# RpiXBeeDaughter.net
KiCad netlist of a schematic drawn in EAGLE
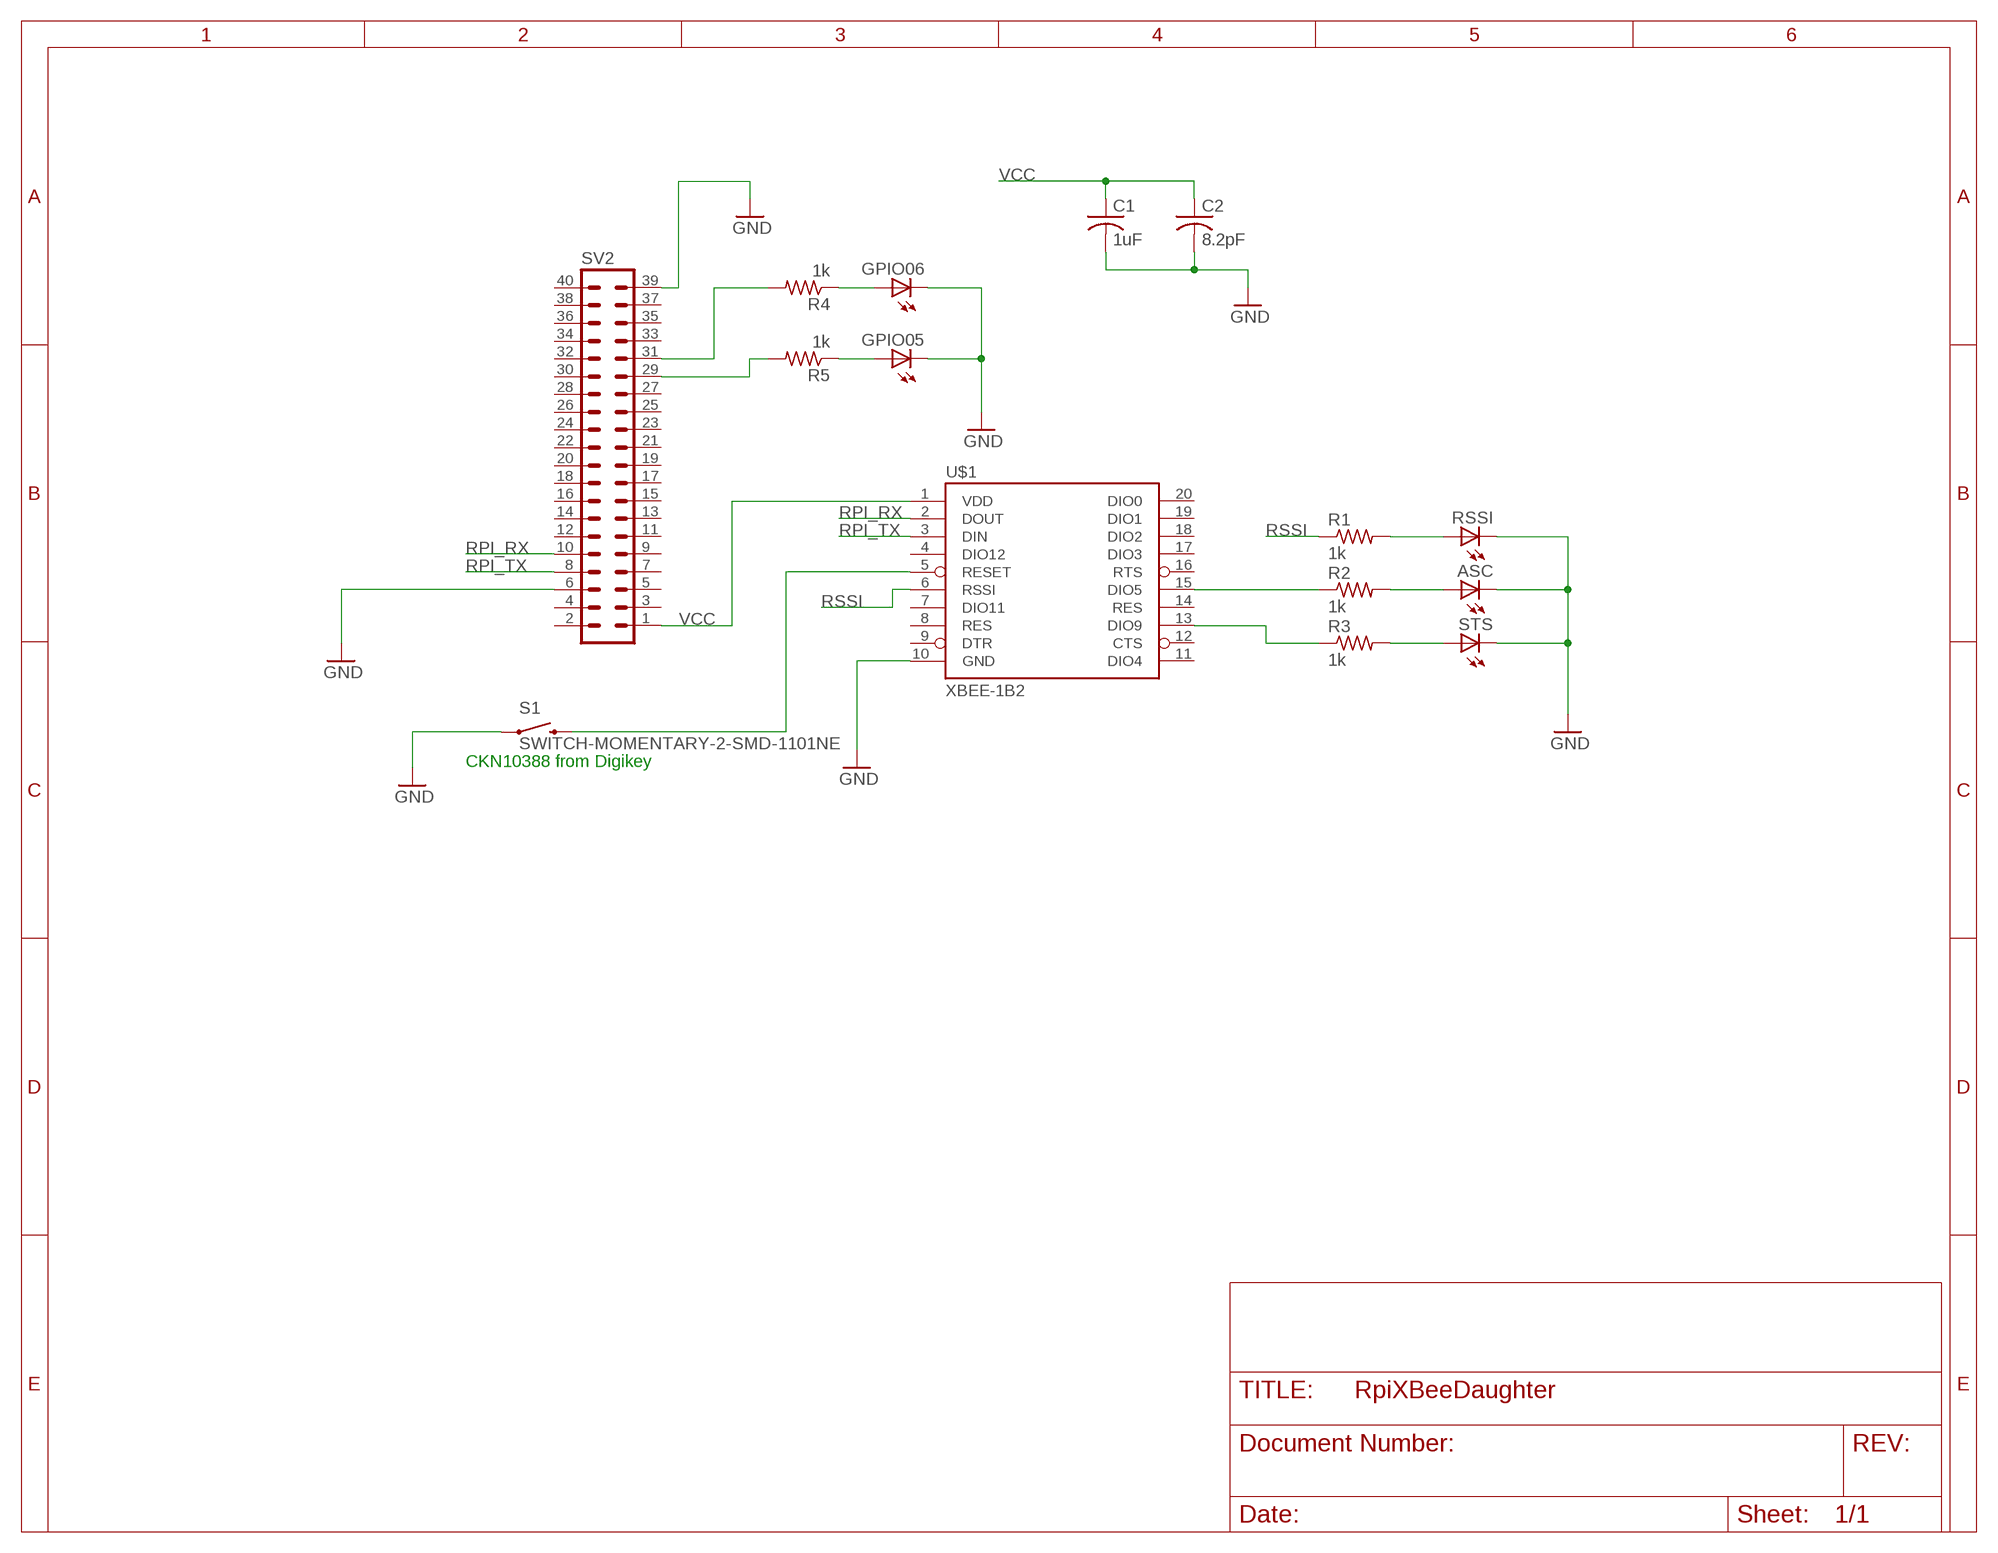
[diagram p0: schematic, sheet 1]

(export (version "E")
  (design (tool "Eeschema 10.0.6"))
  (components
    (comp (ref "ASC")
      (value "LEDCHIP-LED0603")
      (footprint "eagle-import:CHIP-LED0603")
      (libsource (lib "eagle-import") (part "LEDCHIP-LED0603"))
    )
    (comp (ref "C1")
      (value "1uF")
      (footprint "eagle-import:C0805")
      (libsource (lib "eagle-import") (part "C-USC0805"))
    )
    (comp (ref "C2")
      (value "8.2pF")
      (footprint "eagle-import:C0603")
      (libsource (lib "eagle-import") (part "C-USC0603"))
    )
    (comp (ref "GPIO05")
      (value "LEDCHIP-LED0603")
      (footprint "eagle-import:CHIP-LED0603")
      (libsource (lib "eagle-import") (part "LEDCHIP-LED0603"))
    )
    (comp (ref "GPIO06")
      (value "LEDCHIP-LED0603")
      (footprint "eagle-import:CHIP-LED0603")
      (libsource (lib "eagle-import") (part "LEDCHIP-LED0603"))
    )
    (comp (ref "R1")
      (value "1k")
      (footprint "eagle-import:R0603")
      (libsource (lib "eagle-import") (part "R-US_R0603"))
    )
    (comp (ref "R2")
      (value "1k")
      (footprint "eagle-import:R0603")
      (libsource (lib "eagle-import") (part "R-US_R0603"))
    )
    (comp (ref "R3")
      (value "1k")
      (footprint "eagle-import:R0603")
      (libsource (lib "eagle-import") (part "R-US_R0603"))
    )
    (comp (ref "R4")
      (value "1k")
      (footprint "eagle-import:R0603")
      (libsource (lib "eagle-import") (part "R-US_R0603"))
    )
    (comp (ref "R5")
      (value "1k")
      (footprint "eagle-import:R0603")
      (libsource (lib "eagle-import") (part "R-US_R0603"))
    )
    (comp (ref "RSSI")
      (value "LEDCHIP-LED0603")
      (footprint "eagle-import:CHIP-LED0603")
      (libsource (lib "eagle-import") (part "LEDCHIP-LED0603"))
    )
    (comp (ref "S1")
      (value "SWITCH-MOMENTARY-2-SMD-1101NE")
      (footprint "eagle-import:TACTILE-SWITCH-1101NE")
      (libsource (lib "eagle-import") (part "SWITCH-MOMENTARY-2-SMD-1101NE"))
    )
    (comp (ref "STS")
      (value "LEDCHIP-LED0603")
      (footprint "eagle-import:CHIP-LED0603")
      (libsource (lib "eagle-import") (part "LEDCHIP-LED0603"))
    )
    (comp (ref "SV2")
      (value "MA20-2")
      (footprint "eagle-import:MA20-2")
      (libsource (lib "eagle-import") (part "MA20-2"))
    )
    (comp (ref "U$1")
      (value "XBEE-1B2")
      (footprint "eagle-import:XBEE-SILK")
      (libsource (lib "eagle-import") (part "XBEE-1B2"))
    )
  )
  (nets
    (net (code "1") (name "/RPI_RX") (class "Default")
      (node (ref "SV2") (pin "10") (pinfunction "10_10") (pintype "passive"))
      (node (ref "U$1") (pin "2") (pinfunction "DOUT_2") (pintype "output"))
    )
    (net (code "2") (name "/RPI_TX") (class "Default")
      (node (ref "SV2") (pin "8") (pinfunction "8_8") (pintype "passive"))
      (node (ref "U$1") (pin "3") (pinfunction "DIN_3") (pintype "input"))
    )
    (net (code "3") (name "/RSSI") (class "Default")
      (node (ref "R1") (pin "1") (pinfunction "1_1") (pintype "passive"))
      (node (ref "U$1") (pin "6") (pinfunction "RSSI_6") (pintype "bidirectional"))
    )
    (net (code "4") (name "/VCC") (class "Default")
      (node (ref "C1") (pin "1") (pinfunction "1_1") (pintype "passive"))
      (node (ref "C2") (pin "1") (pinfunction "1_1") (pintype "passive"))
      (node (ref "SV2") (pin "1") (pinfunction "1_1") (pintype "passive"))
      (node (ref "U$1") (pin "1") (pinfunction "VDD_1") (pintype "power_in"))
    )
    (net (code "5") (name "GND") (class "Default")
      (node (ref "ASC") (pin "C") (pinfunction "C_C") (pintype "passive"))
      (node (ref "C1") (pin "2") (pinfunction "2_2") (pintype "passive"))
      (node (ref "C2") (pin "2") (pinfunction "2_2") (pintype "passive"))
      (node (ref "GPIO05") (pin "C") (pinfunction "C_C") (pintype "passive"))
      (node (ref "GPIO06") (pin "C") (pinfunction "C_C") (pintype "passive"))
      (node (ref "RSSI") (pin "C") (pinfunction "C_C") (pintype "passive"))
      (node (ref "S1") (pin "P$1") (pinfunction "1_P$1") (pintype "passive"))
      (node (ref "STS") (pin "C") (pinfunction "C_C") (pintype "passive"))
      (node (ref "SV2") (pin "39") (pinfunction "39_39") (pintype "passive"))
      (node (ref "SV2") (pin "6") (pinfunction "6_6") (pintype "passive"))
      (node (ref "U$1") (pin "10") (pinfunction "GND_10") (pintype "power_in"))
    )
    (net (code "6") (name "Net-(ASC-PadA)") (class "Default")
      (node (ref "ASC") (pin "A") (pinfunction "A_A") (pintype "passive"))
      (node (ref "R2") (pin "2") (pinfunction "2_2") (pintype "passive"))
    )
    (net (code "7") (name "Net-(GPIO05-PadA)") (class "Default")
      (node (ref "GPIO05") (pin "A") (pinfunction "A_A") (pintype "passive"))
      (node (ref "R5") (pin "1") (pinfunction "1_1") (pintype "passive"))
    )
    (net (code "8") (name "Net-(GPIO06-PadA)") (class "Default")
      (node (ref "GPIO06") (pin "A") (pinfunction "A_A") (pintype "passive"))
      (node (ref "R4") (pin "1") (pinfunction "1_1") (pintype "passive"))
    )
    (net (code "9") (name "Net-(R1-Pad2)") (class "Default")
      (node (ref "R1") (pin "2") (pinfunction "2_2") (pintype "passive"))
      (node (ref "RSSI") (pin "A") (pinfunction "A_A") (pintype "passive"))
    )
    (net (code "10") (name "Net-(R3-Pad2)") (class "Default")
      (node (ref "R3") (pin "2") (pinfunction "2_2") (pintype "passive"))
      (node (ref "STS") (pin "A") (pinfunction "A_A") (pintype "passive"))
    )
    (net (code "11") (name "Net-(R4-Pad2)") (class "Default")
      (node (ref "R4") (pin "2") (pinfunction "2_2") (pintype "passive"))
      (node (ref "SV2") (pin "31") (pinfunction "31_31") (pintype "passive"))
    )
    (net (code "12") (name "Net-(R5-Pad2)") (class "Default")
      (node (ref "R5") (pin "2") (pinfunction "2_2") (pintype "passive"))
      (node (ref "SV2") (pin "29") (pinfunction "29_29") (pintype "passive"))
    )
    (net (code "13") (name "Net-(S1-2)") (class "Default")
      (node (ref "S1") (pin "P$2") (pinfunction "2_P$2") (pintype "passive"))
      (node (ref "U$1") (pin "5") (pinfunction "RESET_5") (pintype "input"))
    )
    (net (code "14") (name "Net-(U$1-DIO5)") (class "Default")
      (node (ref "R2") (pin "1") (pinfunction "1_1") (pintype "passive"))
      (node (ref "U$1") (pin "15") (pinfunction "DIO5_15") (pintype "bidirectional"))
    )
    (net (code "15") (name "Net-(U$1-DIO9)") (class "Default")
      (node (ref "R3") (pin "1") (pinfunction "1_1") (pintype "passive"))
      (node (ref "U$1") (pin "13") (pinfunction "DIO9_13") (pintype "bidirectional"))
    )
    (net (code "16") (name "unconnected-(SV2-Pad2)") (class "Default")
      (node (ref "SV2") (pin "2") (pinfunction "2_2") (pintype "passive"))
    )
    (net (code "17") (name "unconnected-(SV2-Pad3)") (class "Default")
      (node (ref "SV2") (pin "3") (pinfunction "3_3") (pintype "passive"))
    )
    (net (code "18") (name "unconnected-(SV2-Pad4)") (class "Default")
      (node (ref "SV2") (pin "4") (pinfunction "4_4") (pintype "passive"))
    )
    (net (code "19") (name "unconnected-(SV2-Pad5)") (class "Default")
      (node (ref "SV2") (pin "5") (pinfunction "5_5") (pintype "passive"))
    )
    (net (code "20") (name "unconnected-(SV2-Pad7)") (class "Default")
      (node (ref "SV2") (pin "7") (pinfunction "7_7") (pintype "passive"))
    )
    (net (code "21") (name "unconnected-(SV2-Pad9)") (class "Default")
      (node (ref "SV2") (pin "9") (pinfunction "9_9") (pintype "passive"))
    )
    (net (code "22") (name "unconnected-(SV2-Pad11)") (class "Default")
      (node (ref "SV2") (pin "11") (pinfunction "11_11") (pintype "passive"))
    )
    (net (code "23") (name "unconnected-(SV2-Pad12)") (class "Default")
      (node (ref "SV2") (pin "12") (pinfunction "12_12") (pintype "passive"))
    )
    (net (code "24") (name "unconnected-(SV2-Pad13)") (class "Default")
      (node (ref "SV2") (pin "13") (pinfunction "13_13") (pintype "passive"))
    )
    (net (code "25") (name "unconnected-(SV2-Pad14)") (class "Default")
      (node (ref "SV2") (pin "14") (pinfunction "14_14") (pintype "passive"))
    )
    (net (code "26") (name "unconnected-(SV2-Pad15)") (class "Default")
      (node (ref "SV2") (pin "15") (pinfunction "15_15") (pintype "passive"))
    )
    (net (code "27") (name "unconnected-(SV2-Pad16)") (class "Default")
      (node (ref "SV2") (pin "16") (pinfunction "16_16") (pintype "passive"))
    )
    (net (code "28") (name "unconnected-(SV2-Pad17)") (class "Default")
      (node (ref "SV2") (pin "17") (pinfunction "17_17") (pintype "passive"))
    )
    (net (code "29") (name "unconnected-(SV2-Pad18)") (class "Default")
      (node (ref "SV2") (pin "18") (pinfunction "18_18") (pintype "passive"))
    )
    (net (code "30") (name "unconnected-(SV2-Pad19)") (class "Default")
      (node (ref "SV2") (pin "19") (pinfunction "19_19") (pintype "passive"))
    )
    (net (code "31") (name "unconnected-(SV2-Pad20)") (class "Default")
      (node (ref "SV2") (pin "20") (pinfunction "20_20") (pintype "passive"))
    )
    (net (code "32") (name "unconnected-(SV2-Pad21)") (class "Default")
      (node (ref "SV2") (pin "21") (pinfunction "21_21") (pintype "passive"))
    )
    (net (code "33") (name "unconnected-(SV2-Pad22)") (class "Default")
      (node (ref "SV2") (pin "22") (pinfunction "22_22") (pintype "passive"))
    )
    (net (code "34") (name "unconnected-(SV2-Pad23)") (class "Default")
      (node (ref "SV2") (pin "23") (pinfunction "23_23") (pintype "passive"))
    )
    (net (code "35") (name "unconnected-(SV2-Pad24)") (class "Default")
      (node (ref "SV2") (pin "24") (pinfunction "24_24") (pintype "passive"))
    )
    (net (code "36") (name "unconnected-(SV2-Pad25)") (class "Default")
      (node (ref "SV2") (pin "25") (pinfunction "25_25") (pintype "passive"))
    )
    (net (code "37") (name "unconnected-(SV2-Pad26)") (class "Default")
      (node (ref "SV2") (pin "26") (pinfunction "26_26") (pintype "passive"))
    )
    (net (code "38") (name "unconnected-(SV2-Pad27)") (class "Default")
      (node (ref "SV2") (pin "27") (pinfunction "27_27") (pintype "passive"))
    )
    (net (code "39") (name "unconnected-(SV2-Pad28)") (class "Default")
      (node (ref "SV2") (pin "28") (pinfunction "28_28") (pintype "passive"))
    )
    (net (code "40") (name "unconnected-(SV2-Pad30)") (class "Default")
      (node (ref "SV2") (pin "30") (pinfunction "30_30") (pintype "passive"))
    )
    (net (code "41") (name "unconnected-(SV2-Pad32)") (class "Default")
      (node (ref "SV2") (pin "32") (pinfunction "32_32") (pintype "passive"))
    )
    (net (code "42") (name "unconnected-(SV2-Pad33)") (class "Default")
      (node (ref "SV2") (pin "33") (pinfunction "33_33") (pintype "passive"))
    )
    (net (code "43") (name "unconnected-(SV2-Pad34)") (class "Default")
      (node (ref "SV2") (pin "34") (pinfunction "34_34") (pintype "passive"))
    )
    (net (code "44") (name "unconnected-(SV2-Pad35)") (class "Default")
      (node (ref "SV2") (pin "35") (pinfunction "35_35") (pintype "passive"))
    )
    (net (code "45") (name "unconnected-(SV2-Pad36)") (class "Default")
      (node (ref "SV2") (pin "36") (pinfunction "36_36") (pintype "passive"))
    )
    (net (code "46") (name "unconnected-(SV2-Pad37)") (class "Default")
      (node (ref "SV2") (pin "37") (pinfunction "37_37") (pintype "passive"))
    )
    (net (code "47") (name "unconnected-(SV2-Pad38)") (class "Default")
      (node (ref "SV2") (pin "38") (pinfunction "38_38") (pintype "passive"))
    )
    (net (code "48") (name "unconnected-(SV2-Pad40)") (class "Default")
      (node (ref "SV2") (pin "40") (pinfunction "40_40") (pintype "passive"))
    )
    (net (code "49") (name "unconnected-(U$1-CTS-Pad12)") (class "Default")
      (node (ref "U$1") (pin "12") (pinfunction "CTS_12") (pintype "output"))
    )
    (net (code "50") (name "unconnected-(U$1-DIO0-Pad20)") (class "Default")
      (node (ref "U$1") (pin "20") (pinfunction "DIO0_20") (pintype "bidirectional"))
    )
    (net (code "51") (name "unconnected-(U$1-DIO1-Pad19)") (class "Default")
      (node (ref "U$1") (pin "19") (pinfunction "DIO1_19") (pintype "bidirectional"))
    )
    (net (code "52") (name "unconnected-(U$1-DIO2-Pad18)") (class "Default")
      (node (ref "U$1") (pin "18") (pinfunction "DIO2_18") (pintype "bidirectional"))
    )
    (net (code "53") (name "unconnected-(U$1-DIO3-Pad17)") (class "Default")
      (node (ref "U$1") (pin "17") (pinfunction "DIO3_17") (pintype "bidirectional"))
    )
    (net (code "54") (name "unconnected-(U$1-DIO4-Pad11)") (class "Default")
      (node (ref "U$1") (pin "11") (pinfunction "DIO4_11") (pintype "bidirectional"))
    )
    (net (code "55") (name "unconnected-(U$1-DIO11-Pad7)") (class "Default")
      (node (ref "U$1") (pin "7") (pinfunction "DIO11_7") (pintype "bidirectional"))
    )
    (net (code "56") (name "unconnected-(U$1-DIO12-Pad4)") (class "Default")
      (node (ref "U$1") (pin "4") (pinfunction "DIO12_4") (pintype "bidirectional"))
    )
    (net (code "57") (name "unconnected-(U$1-DTR-Pad9)") (class "Default")
      (node (ref "U$1") (pin "9") (pinfunction "DTR_9") (pintype "bidirectional"))
    )
    (net (code "58") (name "unconnected-(U$1-RES-Pad8)") (class "Default")
      (node (ref "U$1") (pin "8") (pinfunction "RES_8") (pintype "bidirectional"))
    )
    (net (code "59") (name "unconnected-(U$1-RES-Pad14)") (class "Default")
      (node (ref "U$1") (pin "14") (pinfunction "RES_14") (pintype "bidirectional"))
    )
    (net (code "60") (name "unconnected-(U$1-RTS-Pad16)") (class "Default")
      (node (ref "U$1") (pin "16") (pinfunction "RTS_16") (pintype "input"))
    )
  )
)
